# MCISO-S04-V00-Microcontroller.net
KiCad netlist of a schematic drawn in Altium Designer
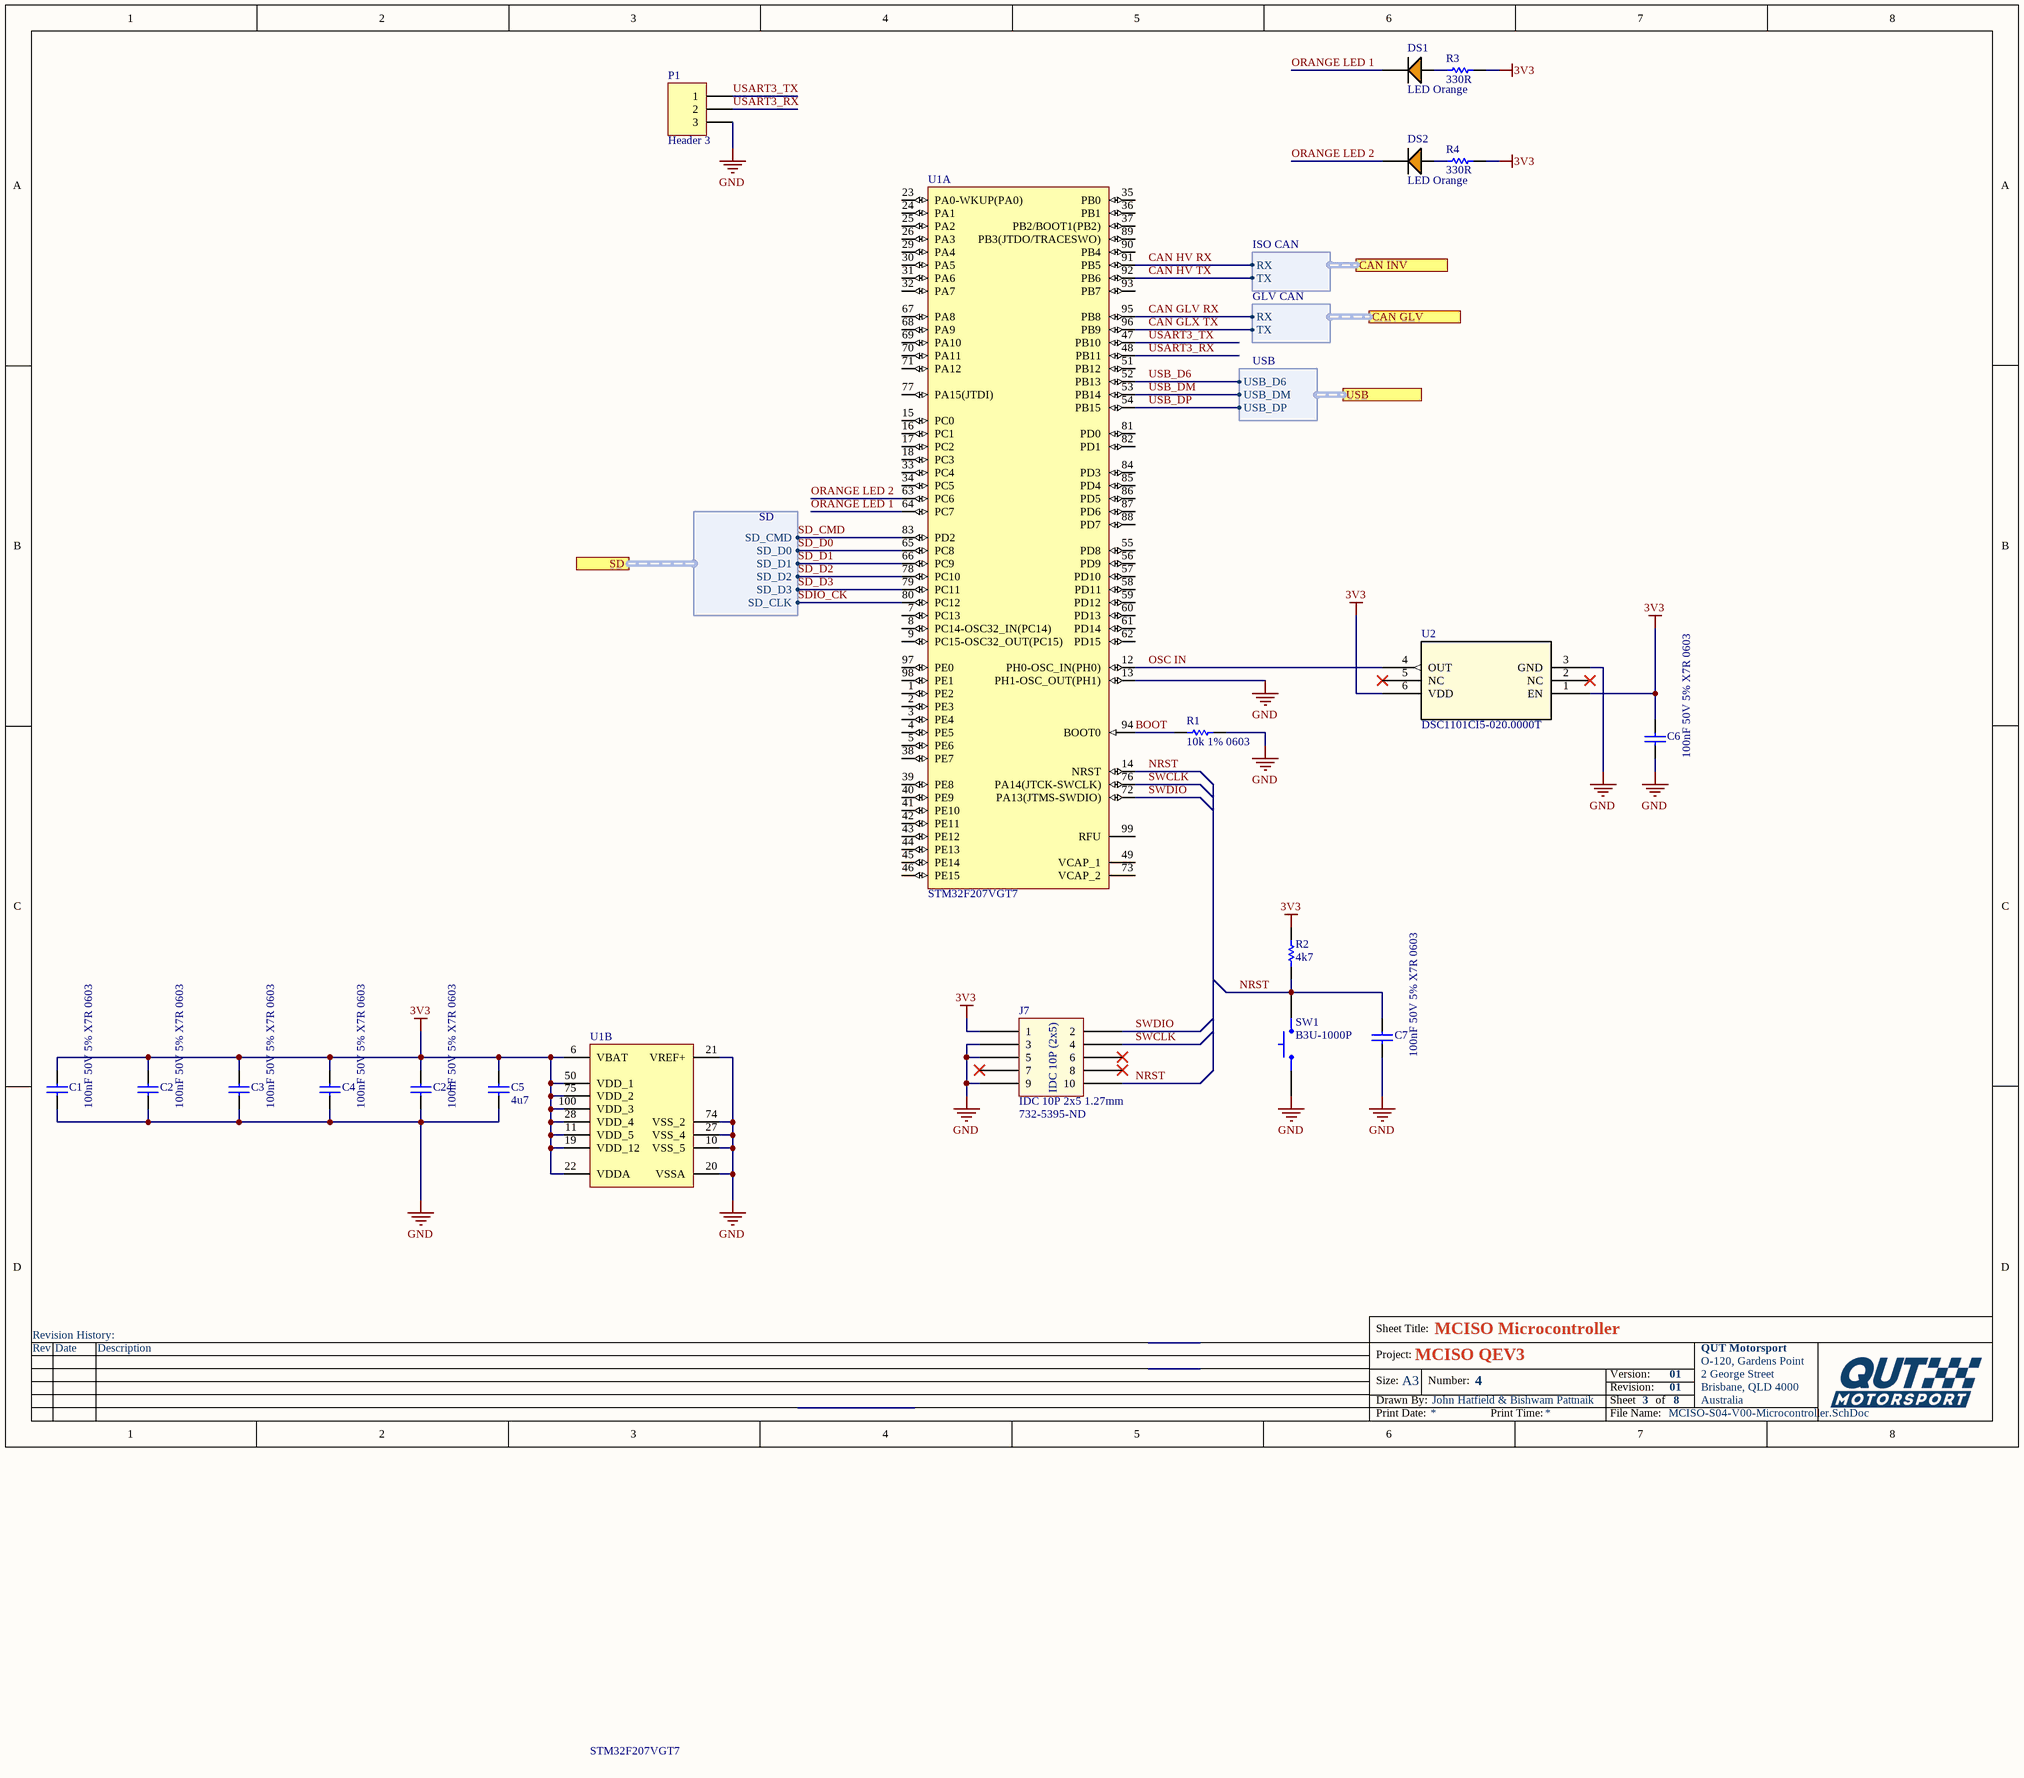
[diagram p0: MCISO-S04-V00-Microcontroller.SchDoc]

(export (version "E")
  (design (tool "Eeschema 10.0.6"))
  (components
    (comp (ref "C1")
      (value "100nF 50V 5% X7R 0603")
      (footprint "Cap_Ceramic_0603")
      (description "Capacitor, Ceramic, SMD, 100nF, 50V, 5%, X7R, 0603")
      (libsource (lib "StandardCapacitors") (part "100nF 50V 5% X7R 0603"))
    )
    (comp (ref "C2")
      (value "100nF 50V 5% X7R 0603")
      (footprint "Cap_Ceramic_0603")
      (description "Capacitor, Ceramic, SMD, 100nF, 50V, 5%, X7R, 0603")
      (libsource (lib "StandardCapacitors") (part "100nF 50V 5% X7R 0603"))
    )
    (comp (ref "C3")
      (value "100nF 50V 5% X7R 0603")
      (footprint "Cap_Ceramic_0603")
      (description "Capacitor, Ceramic, SMD, 100nF, 50V, 5%, X7R, 0603")
      (libsource (lib "StandardCapacitors") (part "100nF 50V 5% X7R 0603"))
    )
    (comp (ref "C4")
      (value "100nF 50V 5% X7R 0603")
      (footprint "Cap_Ceramic_0603")
      (description "Capacitor, Ceramic, SMD, 100nF, 50V, 5%, X7R, 0603")
      (libsource (lib "StandardCapacitors") (part "100nF 50V 5% X7R 0603"))
    )
    (comp (ref "C5")
      (value "4u7")
      (footprint "Cap_Ceramic_0603")
      (description "Capacitor, Ceramic, SMD, 4u7, 50V, 5%, X7R, 0603")
      (libsource (lib "StandardCapacitors") (part "4u7 50V 5% X7R 0603"))
    )
    (comp (ref "C6")
      (value "100nF 50V 5% X7R 0603")
      (footprint "Cap_Ceramic_0603")
      (description "Capacitor, Ceramic, SMD, 100nF, 50V, 5%, X7R, 0603")
      (libsource (lib "StandardCapacitors") (part "100nF 50V 5% X7R 0603"))
    )
    (comp (ref "C7")
      (value "100nF 50V 5% X7R 0603")
      (footprint "Cap_Ceramic_0603")
      (description "Capacitor, Ceramic, SMD, 100nF, 50V, 5%, X7R, 0603")
      (libsource (lib "StandardCapacitors") (part "100nF 50V 5% X7R 0603"))
    )
    (comp (ref "C24")
      (value "100nF 50V 5% X7R 0603")
      (footprint "Cap_Ceramic_0603")
      (description "Capacitor, Ceramic, SMD, 100nF, 50V, 5%, X7R, 0603")
      (libsource (lib "StandardCapacitors") (part "100nF 50V 5% X7R 0603"))
    )
    (comp (ref "DS1")
      (value "LED Orange")
      (footprint "LED ORANGE 0603")
      (libsource (lib "QUTMS_LEDLibrary") (part "LED ORANGE 0603"))
    )
    (comp (ref "DS2")
      (value "LED Orange")
      (footprint "LED ORANGE 0603")
      (libsource (lib "QUTMS_LEDLibrary") (part "LED ORANGE 0603"))
    )
    (comp (ref "J7")
      (value "IDC 10P 2x5 1.27mm")
      (footprint "IDC 1.27MM 10P")
      (libsource (lib "IDCConnectors") (part "IDC 10P 2x5 1.27mm"))
    )
    (comp (ref "P1")
      (value "Header 3")
      (footprint "HDR1X3")
      (description "Header, 3-Pin")
      (fields (field (name "PUBLISHER") "Altium Limited"))
      (libsource (lib "Miscellaneous Connectors") (part "Header 3"))
    )
    (comp (ref "R1")
      (value "10k 1% 0603")
      (footprint "Res_ThinFilm_0603")
      (description "Resistor, SMD, 20k, 0.1W, 5%, 0603")
      (libsource (lib "QUTMS-MCISOLibrary") (part "20k 1% 0603"))
    )
    (comp (ref "R2")
      (value "4k7")
      (footprint "Res_ThinFilm_0603")
      (description "Resistor, SMD, 4k7, 0.1W, 5%, 0603")
      (libsource (lib "StandardResistors") (part "4k7 5% 0603"))
    )
    (comp (ref "R3")
      (value "330R")
      (footprint "Res_ThinFilm_0603")
      (description "Resistor, SMD, 330R, 0.1W, 5%, 0603")
      (libsource (lib "StandardResistors") (part "330R 5% 0603"))
    )
    (comp (ref "R4")
      (value "330R")
      (footprint "Res_ThinFilm_0603")
      (description "Resistor, SMD, 330R, 0.1W, 5%, 0603")
      (libsource (lib "StandardResistors") (part "330R 5% 0603"))
    )
    (comp (ref "SW1")
      (value "B3U-1000P")
      (footprint "BTN B3U-1000P")
      (description "Omron B3U-1000P Ultra Miniture Switch")
      (libsource (lib "QUTMS_SwitchLibrary") (part "BTN B3U-1000P"))
    )
    (comp (ref "U1")
      (value "STM32F207VGT7")
      (footprint "STM-LQFP100_N")
      (libsource (lib "STM32F207VGT7") (part "STM32F207VGT7-Custom"))
    )
    (comp (ref "U2")
      (value "DSC1101CI5-020.0000T")
      (footprint "VDFN6_3P2X2P5_MCH")
      (description "No Description Available")
      (fields (field (name "COPYRIGHT") "Copyright (C) 2018 Accelerated Designs. All rights reserved"))
      (libsource (lib "DSC1101CI5-020.0000T") (part "DSC1101CI5-020.0000T"))
    )
  )
  (nets
    (net (code "6") (name "/BOOT") (class "Default")
      (node (ref "R1") (pin "1") (pinfunction "1_1") (pintype "passive"))
      (node (ref "U1") (pin "94") (pinfunction "BOOT0_94") (pintype "input"))
    )
    (net (code "7") (name "/CAN GLV RX") (class "Default")
      (node (ref "U1") (pin "95") (pinfunction "PB8_95") (pintype "bidirectional"))
    )
    (net (code "8") (name "/CAN GLX TX") (class "Default")
      (node (ref "U1") (pin "96") (pinfunction "PB9_96") (pintype "bidirectional"))
    )
    (net (code "9") (name "/CAN HV RX") (class "Default")
      (node (ref "U1") (pin "91") (pinfunction "PB5_91") (pintype "bidirectional"))
    )
    (net (code "10") (name "/CAN HV TX") (class "Default")
      (node (ref "U1") (pin "92") (pinfunction "PB6_92") (pintype "bidirectional"))
    )
    (net (code "11") (name "/NRST") (class "Default")
      (node (ref "C7") (pin "2") (pinfunction "2_2") (pintype "passive"))
      (node (ref "J7") (pin "10") (pinfunction "10_10") (pintype "passive"))
      (node (ref "R2") (pin "1") (pinfunction "1_1") (pintype "passive"))
      (node (ref "SW1") (pin "2") (pinfunction "2_2") (pintype "passive"))
      (node (ref "U1") (pin "14") (pinfunction "NRST_14") (pintype "bidirectional"))
    )
    (net (code "12") (name "/ORANGE LED 1") (class "Default")
      (node (ref "DS1") (pin "2") (pinfunction "C_2") (pintype "passive"))
      (node (ref "U1") (pin "64") (pinfunction "PC7_64") (pintype "bidirectional"))
    )
    (net (code "13") (name "/ORANGE LED 2") (class "Default")
      (node (ref "DS2") (pin "2") (pinfunction "C_2") (pintype "passive"))
      (node (ref "U1") (pin "63") (pinfunction "PC6_63") (pintype "bidirectional"))
    )
    (net (code "14") (name "/OSC IN") (class "Default")
      (node (ref "U1") (pin "12") (pinfunction "PH0-OSC_IN(PH0)_12") (pintype "bidirectional"))
      (node (ref "U2") (pin "4") (pinfunction "OUT_4") (pintype "output"))
    )
    (net (code "15") (name "/SDIO_CK") (class "Default")
      (node (ref "U1") (pin "80") (pinfunction "PC12_80") (pintype "bidirectional"))
    )
    (net (code "16") (name "/SD_CMD") (class "Default")
      (node (ref "U1") (pin "83") (pinfunction "PD2_83") (pintype "bidirectional"))
    )
    (net (code "17") (name "/SD_D0") (class "Default")
      (node (ref "U1") (pin "65") (pinfunction "PC8_65") (pintype "bidirectional"))
    )
    (net (code "18") (name "/SD_D1") (class "Default")
      (node (ref "U1") (pin "66") (pinfunction "PC9_66") (pintype "bidirectional"))
    )
    (net (code "19") (name "/SD_D2") (class "Default")
      (node (ref "U1") (pin "78") (pinfunction "PC10_78") (pintype "bidirectional"))
    )
    (net (code "20") (name "/SD_D3") (class "Default")
      (node (ref "U1") (pin "79") (pinfunction "PC11_79") (pintype "bidirectional"))
    )
    (net (code "21") (name "/SWCLK") (class "Default")
      (node (ref "J7") (pin "4") (pinfunction "4_4") (pintype "passive"))
      (node (ref "U1") (pin "76") (pinfunction "PA14(JTCK-SWCLK)_76") (pintype "bidirectional"))
    )
    (net (code "22") (name "/SWDIO") (class "Default")
      (node (ref "J7") (pin "2") (pinfunction "2_2") (pintype "passive"))
      (node (ref "U1") (pin "72") (pinfunction "PA13(JTMS-SWDIO)_72") (pintype "bidirectional"))
    )
    (net (code "23") (name "/USART3_RX") (class "Default")
      (node (ref "P1") (pin "2") (pinfunction "2_2") (pintype "passive"))
      (node (ref "U1") (pin "48") (pinfunction "PB11_48") (pintype "bidirectional"))
    )
    (net (code "24") (name "/USART3_TX") (class "Default")
      (node (ref "P1") (pin "1") (pinfunction "1_1") (pintype "passive"))
      (node (ref "U1") (pin "47") (pinfunction "PB10_47") (pintype "bidirectional"))
    )
    (net (code "25") (name "/USB_D6") (class "Default")
      (node (ref "U1") (pin "52") (pinfunction "PB13_52") (pintype "bidirectional"))
    )
    (net (code "26") (name "/USB_DM") (class "Default")
      (node (ref "U1") (pin "53") (pinfunction "PB14_53") (pintype "bidirectional"))
    )
    (net (code "27") (name "/USB_DP") (class "Default")
      (node (ref "U1") (pin "54") (pinfunction "PB15_54") (pintype "bidirectional"))
    )
    (net (code "32") (name "3V3") (class "Default")
      (node (ref "C1") (pin "2") (pinfunction "2_2") (pintype "passive"))
      (node (ref "C2") (pin "2") (pinfunction "2_2") (pintype "passive"))
      (node (ref "C24") (pin "2") (pinfunction "2_2") (pintype "passive"))
      (node (ref "C3") (pin "2") (pinfunction "2_2") (pintype "passive"))
      (node (ref "C4") (pin "2") (pinfunction "2_2") (pintype "passive"))
      (node (ref "C5") (pin "2") (pinfunction "2_2") (pintype "passive"))
      (node (ref "C6") (pin "2") (pinfunction "2_2") (pintype "passive"))
      (node (ref "J7") (pin "1") (pinfunction "1_1") (pintype "passive"))
      (node (ref "R2") (pin "2") (pinfunction "2_2") (pintype "passive"))
      (node (ref "R3") (pin "2") (pinfunction "2_2") (pintype "passive"))
      (node (ref "R4") (pin "2") (pinfunction "2_2") (pintype "passive"))
      (node (ref "U1") (pin "100") (pinfunction "VDD_3_100") (pintype "power_in"))
      (node (ref "U1") (pin "11") (pinfunction "VDD_5_11") (pintype "power_in"))
      (node (ref "U1") (pin "19") (pinfunction "VDD_12_19") (pintype "power_in"))
      (node (ref "U1") (pin "22") (pinfunction "VDDA_22") (pintype "power_in"))
      (node (ref "U1") (pin "28") (pinfunction "VDD_4_28") (pintype "power_in"))
      (node (ref "U1") (pin "50") (pinfunction "VDD_1_50") (pintype "power_in"))
      (node (ref "U1") (pin "6") (pinfunction "VBAT_6") (pintype "power_in"))
      (node (ref "U1") (pin "75") (pinfunction "VDD_2_75") (pintype "power_in"))
      (node (ref "U2") (pin "1") (pinfunction "EN_1") (pintype "passive"))
      (node (ref "U2") (pin "6") (pinfunction "VDD_6") (pintype "power_in"))
    )
    (net (code "33") (name "GND") (class "Default")
      (node (ref "C1") (pin "1") (pinfunction "1_1") (pintype "passive"))
      (node (ref "C2") (pin "1") (pinfunction "1_1") (pintype "passive"))
      (node (ref "C24") (pin "1") (pinfunction "1_1") (pintype "passive"))
      (node (ref "C3") (pin "1") (pinfunction "1_1") (pintype "passive"))
      (node (ref "C4") (pin "1") (pinfunction "1_1") (pintype "passive"))
      (node (ref "C5") (pin "1") (pinfunction "1_1") (pintype "passive"))
      (node (ref "C6") (pin "1") (pinfunction "1_1") (pintype "passive"))
      (node (ref "C7") (pin "1") (pinfunction "1_1") (pintype "passive"))
      (node (ref "J7") (pin "3") (pinfunction "3_3") (pintype "passive"))
      (node (ref "J7") (pin "5") (pinfunction "5_5") (pintype "passive"))
      (node (ref "J7") (pin "9") (pinfunction "9_9") (pintype "passive"))
      (node (ref "P1") (pin "3") (pinfunction "3_3") (pintype "passive"))
      (node (ref "R1") (pin "2") (pinfunction "2_2") (pintype "passive"))
      (node (ref "SW1") (pin "1") (pinfunction "1_1") (pintype "passive"))
      (node (ref "U1") (pin "10") (pinfunction "VSS_5_10") (pintype "power_in"))
      (node (ref "U1") (pin "13") (pinfunction "PH1-OSC_OUT(PH1)_13") (pintype "bidirectional"))
      (node (ref "U1") (pin "20") (pinfunction "VSSA_20") (pintype "power_in"))
      (node (ref "U1") (pin "21") (pinfunction "VREF+_21") (pintype "power_in"))
      (node (ref "U1") (pin "27") (pinfunction "VSS_4_27") (pintype "power_in"))
      (node (ref "U1") (pin "74") (pinfunction "VSS_2_74") (pintype "power_in"))
      (node (ref "U2") (pin "3") (pinfunction "GND_3") (pintype "passive"))
    )
    (net (code "34") (name "Net-(DS1-A)") (class "Default")
      (node (ref "DS1") (pin "1") (pinfunction "A_1") (pintype "passive"))
      (node (ref "R3") (pin "1") (pinfunction "1_1") (pintype "passive"))
    )
    (net (code "35") (name "Net-(DS2-A)") (class "Default")
      (node (ref "DS2") (pin "1") (pinfunction "A_1") (pintype "passive"))
      (node (ref "R4") (pin "1") (pinfunction "1_1") (pintype "passive"))
    )
    (net (code "36") (name "unconnected-(J7-Pad6)") (class "Default")
      (node (ref "J7") (pin "6") (pinfunction "6_6") (pintype "passive+no_connect"))
    )
    (net (code "37") (name "unconnected-(J7-Pad7)") (class "Default")
      (node (ref "J7") (pin "7") (pinfunction "7_7") (pintype "passive+no_connect"))
    )
    (net (code "38") (name "unconnected-(J7-Pad8)") (class "Default")
      (node (ref "J7") (pin "8") (pinfunction "8_8") (pintype "passive+no_connect"))
    )
    (net (code "39") (name "unconnected-(U1A-PA0-WKUP(PA0)-Pad23)") (class "Default")
      (node (ref "U1") (pin "23") (pinfunction "PA0-WKUP(PA0)_23") (pintype "bidirectional"))
    )
    (net (code "40") (name "unconnected-(U1A-PA1-Pad24)") (class "Default")
      (node (ref "U1") (pin "24") (pinfunction "PA1_24") (pintype "bidirectional"))
    )
    (net (code "41") (name "unconnected-(U1A-PA2-Pad25)") (class "Default")
      (node (ref "U1") (pin "25") (pinfunction "PA2_25") (pintype "bidirectional"))
    )
    (net (code "42") (name "unconnected-(U1A-PA3-Pad26)") (class "Default")
      (node (ref "U1") (pin "26") (pinfunction "PA3_26") (pintype "bidirectional"))
    )
    (net (code "43") (name "unconnected-(U1A-PA4-Pad29)") (class "Default")
      (node (ref "U1") (pin "29") (pinfunction "PA4_29") (pintype "bidirectional"))
    )
    (net (code "44") (name "unconnected-(U1A-PA5-Pad30)") (class "Default")
      (node (ref "U1") (pin "30") (pinfunction "PA5_30") (pintype "bidirectional"))
    )
    (net (code "45") (name "unconnected-(U1A-PA6-Pad31)") (class "Default")
      (node (ref "U1") (pin "31") (pinfunction "PA6_31") (pintype "bidirectional"))
    )
    (net (code "46") (name "unconnected-(U1A-PA7-Pad32)") (class "Default")
      (node (ref "U1") (pin "32") (pinfunction "PA7_32") (pintype "bidirectional"))
    )
    (net (code "47") (name "unconnected-(U1A-PA8-Pad67)") (class "Default")
      (node (ref "U1") (pin "67") (pinfunction "PA8_67") (pintype "bidirectional"))
    )
    (net (code "48") (name "unconnected-(U1A-PA9-Pad68)") (class "Default")
      (node (ref "U1") (pin "68") (pinfunction "PA9_68") (pintype "bidirectional"))
    )
    (net (code "49") (name "unconnected-(U1A-PA10-Pad69)") (class "Default")
      (node (ref "U1") (pin "69") (pinfunction "PA10_69") (pintype "bidirectional"))
    )
    (net (code "50") (name "unconnected-(U1A-PA11-Pad70)") (class "Default")
      (node (ref "U1") (pin "70") (pinfunction "PA11_70") (pintype "bidirectional"))
    )
    (net (code "51") (name "unconnected-(U1A-PA12-Pad71)") (class "Default")
      (node (ref "U1") (pin "71") (pinfunction "PA12_71") (pintype "bidirectional"))
    )
    (net (code "52") (name "unconnected-(U1A-PA15(JTDI)-Pad77)") (class "Default")
      (node (ref "U1") (pin "77") (pinfunction "PA15(JTDI)_77") (pintype "bidirectional"))
    )
    (net (code "53") (name "unconnected-(U1A-PB0-Pad35)") (class "Default")
      (node (ref "U1") (pin "35") (pinfunction "PB0_35") (pintype "bidirectional"))
    )
    (net (code "54") (name "unconnected-(U1A-PB1-Pad36)") (class "Default")
      (node (ref "U1") (pin "36") (pinfunction "PB1_36") (pintype "bidirectional"))
    )
    (net (code "55") (name "unconnected-(U1A-PB2{slash}BOOT1(PB2)-Pad37)") (class "Default")
      (node (ref "U1") (pin "37") (pinfunction "PB2/BOOT1(PB2)_37") (pintype "bidirectional"))
    )
    (net (code "56") (name "unconnected-(U1A-PB3(JTDO{slash}TRACESWO)-Pad89)") (class "Default")
      (node (ref "U1") (pin "89") (pinfunction "PB3(JTDO/TRACESWO)_89") (pintype "bidirectional"))
    )
    (net (code "57") (name "unconnected-(U1A-PB4-Pad90)") (class "Default")
      (node (ref "U1") (pin "90") (pinfunction "PB4_90") (pintype "bidirectional"))
    )
    (net (code "58") (name "unconnected-(U1A-PB7-Pad93)") (class "Default")
      (node (ref "U1") (pin "93") (pinfunction "PB7_93") (pintype "bidirectional"))
    )
    (net (code "59") (name "unconnected-(U1A-PB12-Pad51)") (class "Default")
      (node (ref "U1") (pin "51") (pinfunction "PB12_51") (pintype "bidirectional"))
    )
    (net (code "60") (name "unconnected-(U1A-PC0-Pad15)") (class "Default")
      (node (ref "U1") (pin "15") (pinfunction "PC0_15") (pintype "bidirectional"))
    )
    (net (code "61") (name "unconnected-(U1A-PC1-Pad16)") (class "Default")
      (node (ref "U1") (pin "16") (pinfunction "PC1_16") (pintype "bidirectional"))
    )
    (net (code "62") (name "unconnected-(U1A-PC2-Pad17)") (class "Default")
      (node (ref "U1") (pin "17") (pinfunction "PC2_17") (pintype "bidirectional"))
    )
    (net (code "63") (name "unconnected-(U1A-PC3-Pad18)") (class "Default")
      (node (ref "U1") (pin "18") (pinfunction "PC3_18") (pintype "bidirectional"))
    )
    (net (code "64") (name "unconnected-(U1A-PC4-Pad33)") (class "Default")
      (node (ref "U1") (pin "33") (pinfunction "PC4_33") (pintype "bidirectional"))
    )
    (net (code "65") (name "unconnected-(U1A-PC5-Pad34)") (class "Default")
      (node (ref "U1") (pin "34") (pinfunction "PC5_34") (pintype "bidirectional"))
    )
    (net (code "66") (name "unconnected-(U1A-PC13-Pad7)") (class "Default")
      (node (ref "U1") (pin "7") (pinfunction "PC13_7") (pintype "bidirectional"))
    )
    (net (code "67") (name "unconnected-(U1A-PC14-OSC32_IN(PC14)-Pad8)") (class "Default")
      (node (ref "U1") (pin "8") (pinfunction "PC14-OSC32_IN(PC14)_8") (pintype "bidirectional"))
    )
    (net (code "68") (name "unconnected-(U1A-PC15-OSC32_OUT(PC15)-Pad9)") (class "Default")
      (node (ref "U1") (pin "9") (pinfunction "PC15-OSC32_OUT(PC15)_9") (pintype "bidirectional"))
    )
    (net (code "69") (name "unconnected-(U1A-PD0-Pad81)") (class "Default")
      (node (ref "U1") (pin "81") (pinfunction "PD0_81") (pintype "bidirectional"))
    )
    (net (code "70") (name "unconnected-(U1A-PD1-Pad82)") (class "Default")
      (node (ref "U1") (pin "82") (pinfunction "PD1_82") (pintype "bidirectional"))
    )
    (net (code "71") (name "unconnected-(U1A-PD3-Pad84)") (class "Default")
      (node (ref "U1") (pin "84") (pinfunction "PD3_84") (pintype "bidirectional"))
    )
    (net (code "72") (name "unconnected-(U1A-PD4-Pad85)") (class "Default")
      (node (ref "U1") (pin "85") (pinfunction "PD4_85") (pintype "bidirectional"))
    )
    (net (code "73") (name "unconnected-(U1A-PD5-Pad86)") (class "Default")
      (node (ref "U1") (pin "86") (pinfunction "PD5_86") (pintype "bidirectional"))
    )
    (net (code "74") (name "unconnected-(U1A-PD6-Pad87)") (class "Default")
      (node (ref "U1") (pin "87") (pinfunction "PD6_87") (pintype "bidirectional"))
    )
    (net (code "75") (name "unconnected-(U1A-PD7-Pad88)") (class "Default")
      (node (ref "U1") (pin "88") (pinfunction "PD7_88") (pintype "bidirectional"))
    )
    (net (code "76") (name "unconnected-(U1A-PD8-Pad55)") (class "Default")
      (node (ref "U1") (pin "55") (pinfunction "PD8_55") (pintype "bidirectional"))
    )
    (net (code "77") (name "unconnected-(U1A-PD9-Pad56)") (class "Default")
      (node (ref "U1") (pin "56") (pinfunction "PD9_56") (pintype "bidirectional"))
    )
    (net (code "78") (name "unconnected-(U1A-PD10-Pad57)") (class "Default")
      (node (ref "U1") (pin "57") (pinfunction "PD10_57") (pintype "bidirectional"))
    )
    (net (code "79") (name "unconnected-(U1A-PD11-Pad58)") (class "Default")
      (node (ref "U1") (pin "58") (pinfunction "PD11_58") (pintype "bidirectional"))
    )
    (net (code "80") (name "unconnected-(U1A-PD12-Pad59)") (class "Default")
      (node (ref "U1") (pin "59") (pinfunction "PD12_59") (pintype "bidirectional"))
    )
    (net (code "81") (name "unconnected-(U1A-PD13-Pad60)") (class "Default")
      (node (ref "U1") (pin "60") (pinfunction "PD13_60") (pintype "bidirectional"))
    )
    (net (code "82") (name "unconnected-(U1A-PD14-Pad61)") (class "Default")
      (node (ref "U1") (pin "61") (pinfunction "PD14_61") (pintype "bidirectional"))
    )
    (net (code "83") (name "unconnected-(U1A-PD15-Pad62)") (class "Default")
      (node (ref "U1") (pin "62") (pinfunction "PD15_62") (pintype "bidirectional"))
    )
    (net (code "84") (name "unconnected-(U1A-PE0-Pad97)") (class "Default")
      (node (ref "U1") (pin "97") (pinfunction "PE0_97") (pintype "bidirectional"))
    )
    (net (code "85") (name "unconnected-(U1A-PE1-Pad98)") (class "Default")
      (node (ref "U1") (pin "98") (pinfunction "PE1_98") (pintype "bidirectional"))
    )
    (net (code "86") (name "unconnected-(U1A-PE2-Pad1)") (class "Default")
      (node (ref "U1") (pin "1") (pinfunction "PE2_1") (pintype "bidirectional"))
    )
    (net (code "87") (name "unconnected-(U1A-PE3-Pad2)") (class "Default")
      (node (ref "U1") (pin "2") (pinfunction "PE3_2") (pintype "bidirectional"))
    )
    (net (code "88") (name "unconnected-(U1A-PE4-Pad3)") (class "Default")
      (node (ref "U1") (pin "3") (pinfunction "PE4_3") (pintype "bidirectional"))
    )
    (net (code "89") (name "unconnected-(U1A-PE5-Pad4)") (class "Default")
      (node (ref "U1") (pin "4") (pinfunction "PE5_4") (pintype "bidirectional"))
    )
    (net (code "90") (name "unconnected-(U1A-PE6-Pad5)") (class "Default")
      (node (ref "U1") (pin "5") (pinfunction "PE6_5") (pintype "bidirectional"))
    )
    (net (code "91") (name "unconnected-(U1A-PE7-Pad38)") (class "Default")
      (node (ref "U1") (pin "38") (pinfunction "PE7_38") (pintype "bidirectional"))
    )
    (net (code "92") (name "unconnected-(U1A-PE8-Pad39)") (class "Default")
      (node (ref "U1") (pin "39") (pinfunction "PE8_39") (pintype "bidirectional"))
    )
    (net (code "93") (name "unconnected-(U1A-PE9-Pad40)") (class "Default")
      (node (ref "U1") (pin "40") (pinfunction "PE9_40") (pintype "bidirectional"))
    )
    (net (code "94") (name "unconnected-(U1A-PE10-Pad41)") (class "Default")
      (node (ref "U1") (pin "41") (pinfunction "PE10_41") (pintype "bidirectional"))
    )
    (net (code "95") (name "unconnected-(U1A-PE11-Pad42)") (class "Default")
      (node (ref "U1") (pin "42") (pinfunction "PE11_42") (pintype "bidirectional"))
    )
    (net (code "96") (name "unconnected-(U1A-PE12-Pad43)") (class "Default")
      (node (ref "U1") (pin "43") (pinfunction "PE12_43") (pintype "bidirectional"))
    )
    (net (code "97") (name "unconnected-(U1A-PE13-Pad44)") (class "Default")
      (node (ref "U1") (pin "44") (pinfunction "PE13_44") (pintype "bidirectional"))
    )
    (net (code "98") (name "unconnected-(U1A-PE14-Pad45)") (class "Default")
      (node (ref "U1") (pin "45") (pinfunction "PE14_45") (pintype "bidirectional"))
    )
    (net (code "99") (name "unconnected-(U1A-PE15-Pad46)") (class "Default")
      (node (ref "U1") (pin "46") (pinfunction "PE15_46") (pintype "bidirectional"))
    )
    (net (code "100") (name "unconnected-(U1A-RFU-Pad99)") (class "Default")
      (node (ref "U1") (pin "99") (pinfunction "RFU_99") (pintype "passive"))
    )
    (net (code "101") (name "unconnected-(U1A-VCAP_1-Pad49)") (class "Default")
      (node (ref "U1") (pin "49") (pinfunction "VCAP_1_49") (pintype "power_in"))
    )
    (net (code "102") (name "unconnected-(U1A-VCAP_2-Pad73)") (class "Default")
      (node (ref "U1") (pin "73") (pinfunction "VCAP_2_73") (pintype "power_in"))
    )
    (net (code "103") (name "unconnected-(U2-NC-Pad2)") (class "Default")
      (node (ref "U2") (pin "2") (pinfunction "NC_2") (pintype "passive+no_connect"))
    )
    (net (code "104") (name "unconnected-(U2-NC-Pad5)") (class "Default")
      (node (ref "U2") (pin "5") (pinfunction "NC_5") (pintype "passive+no_connect"))
    )
  )
)
